# Otomasyon_kart.net
KiCad netlist of a schematic drawn in EAGLE
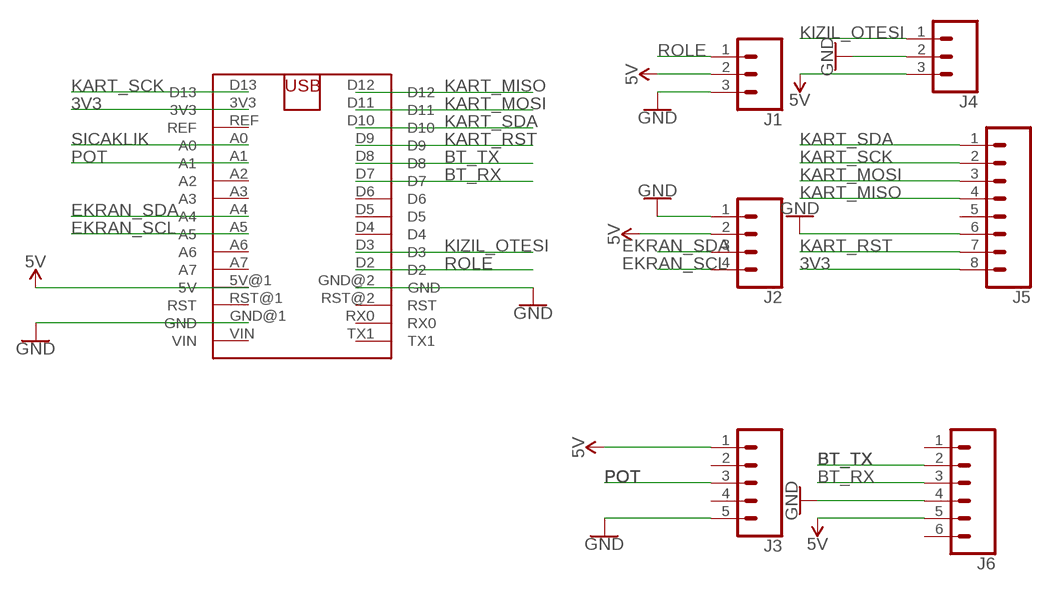
[diagram p0: schematic, sheet 1]

(export (version "E")
  (design (tool "Eeschema 10.0.6"))
  (components
    (comp (ref "J1")
      (value "CONN_03")
      (footprint "eagle-import:1X03")
      (libsource (lib "eagle-import") (part "CONN_03"))
    )
    (comp (ref "J2")
      (value "CONN_04")
      (footprint "eagle-import:1X04")
      (libsource (lib "eagle-import") (part "CONN_04"))
    )
    (comp (ref "J3")
      (value "CONN_05")
      (footprint "eagle-import:1X05")
      (libsource (lib "eagle-import") (part "CONN_05"))
    )
    (comp (ref "J4")
      (value "CONN_03")
      (footprint "eagle-import:1X03")
      (libsource (lib "eagle-import") (part "CONN_03"))
    )
    (comp (ref "J5")
      (value "CONN_08\"")
      (footprint "eagle-import:1X08")
      (libsource (lib "eagle-import") (part "CONN_08{dblquote}"))
    )
    (comp (ref "J6")
      (value "CONN_06LOCK")
      (footprint "eagle-import:1X06_LOCK")
      (libsource (lib "eagle-import") (part "CONN_06LOCK"))
    )
    (comp (ref "U$1")
      (value "ARDUINO_NANO")
      (footprint "eagle-import:ARDUINO_NANO")
      (libsource (lib "eagle-import") (part "ARDUINO_NANO"))
    )
  )
  (nets
    (net (code "1") (name "/3V3") (class "Default")
      (node (ref "J5") (pin "8") (pinfunction "8_8") (pintype "passive"))
      (node (ref "U$1") (pin "3V3") (pinfunction "3V3_3V3") (pintype "bidirectional"))
    )
    (net (code "2") (name "/BT_RX") (class "Default")
      (node (ref "J6") (pin "3") (pinfunction "3_3") (pintype "passive"))
      (node (ref "U$1") (pin "D7") (pinfunction "D7_D7") (pintype "bidirectional"))
    )
    (net (code "3") (name "/BT_TX") (class "Default")
      (node (ref "J6") (pin "2") (pinfunction "2_2") (pintype "passive"))
      (node (ref "U$1") (pin "D8") (pinfunction "D8_D8") (pintype "bidirectional"))
    )
    (net (code "4") (name "/EKRAN_SCL") (class "Default")
      (node (ref "J2") (pin "4") (pinfunction "4_4") (pintype "passive"))
      (node (ref "U$1") (pin "A5") (pinfunction "A5_A5") (pintype "bidirectional"))
    )
    (net (code "5") (name "/EKRAN_SDA") (class "Default")
      (node (ref "J2") (pin "3") (pinfunction "3_3") (pintype "passive"))
      (node (ref "U$1") (pin "A4") (pinfunction "A4_A4") (pintype "bidirectional"))
    )
    (net (code "6") (name "/KART_MISO") (class "Default")
      (node (ref "J5") (pin "4") (pinfunction "4_4") (pintype "passive"))
      (node (ref "U$1") (pin "D12") (pinfunction "D12_D12") (pintype "bidirectional"))
    )
    (net (code "7") (name "/KART_MOSI") (class "Default")
      (node (ref "J5") (pin "3") (pinfunction "3_3") (pintype "passive"))
      (node (ref "U$1") (pin "D11") (pinfunction "D11_D11") (pintype "bidirectional"))
    )
    (net (code "8") (name "/KART_RST") (class "Default")
      (node (ref "J5") (pin "7") (pinfunction "7_7") (pintype "passive"))
      (node (ref "U$1") (pin "D9") (pinfunction "D9_D9") (pintype "bidirectional"))
    )
    (net (code "9") (name "/KART_SCK") (class "Default")
      (node (ref "J5") (pin "2") (pinfunction "2_2") (pintype "passive"))
      (node (ref "U$1") (pin "D13") (pinfunction "D13_D13") (pintype "bidirectional"))
    )
    (net (code "10") (name "/KART_SDA") (class "Default")
      (node (ref "J5") (pin "1") (pinfunction "1_1") (pintype "passive"))
      (node (ref "U$1") (pin "D10") (pinfunction "D10_D10") (pintype "bidirectional"))
    )
    (net (code "11") (name "/KIZIL_OTESI") (class "Default")
      (node (ref "J4") (pin "1") (pinfunction "1_1") (pintype "passive"))
      (node (ref "U$1") (pin "D3") (pinfunction "D3_D3") (pintype "bidirectional"))
    )
    (net (code "12") (name "/POT") (class "Default")
      (node (ref "J3") (pin "3") (pinfunction "3_3") (pintype "passive"))
      (node (ref "U$1") (pin "A1") (pinfunction "A1_A1") (pintype "bidirectional"))
    )
    (net (code "13") (name "/ROLE") (class "Default")
      (node (ref "J1") (pin "1") (pinfunction "1_1") (pintype "passive"))
      (node (ref "U$1") (pin "D2") (pinfunction "D2_D2") (pintype "bidirectional"))
    )
    (net (code "14") (name "/SICAKLIK") (class "Default")
      (node (ref "U$1") (pin "A0") (pinfunction "A0_A0") (pintype "bidirectional"))
    )
    (net (code "15") (name "5V") (class "Default")
      (node (ref "J1") (pin "2") (pinfunction "2_2") (pintype "passive"))
      (node (ref "J2") (pin "2") (pinfunction "2_2") (pintype "passive"))
      (node (ref "J3") (pin "1") (pinfunction "1_1") (pintype "passive"))
      (node (ref "J4") (pin "3") (pinfunction "3_3") (pintype "passive"))
      (node (ref "J6") (pin "5") (pinfunction "5_5") (pintype "passive"))
      (node (ref "U$1") (pin "5V@1") (pinfunction "5V_5V@1") (pintype "bidirectional"))
    )
    (net (code "16") (name "GND") (class "Default")
      (node (ref "J1") (pin "3") (pinfunction "3_3") (pintype "passive"))
      (node (ref "J2") (pin "1") (pinfunction "1_1") (pintype "passive"))
      (node (ref "J3") (pin "5") (pinfunction "5_5") (pintype "passive"))
      (node (ref "J4") (pin "2") (pinfunction "2_2") (pintype "passive"))
      (node (ref "J5") (pin "6") (pinfunction "6_6") (pintype "passive"))
      (node (ref "J6") (pin "4") (pinfunction "4_4") (pintype "passive"))
      (node (ref "U$1") (pin "GND@1") (pinfunction "GND_GND@1") (pintype "bidirectional"))
      (node (ref "U$1") (pin "GND@2") (pinfunction "GND_GND@2") (pintype "bidirectional"))
    )
    (net (code "17") (name "unconnected-(J3-Pad2)") (class "Default")
      (node (ref "J3") (pin "2") (pinfunction "2_2") (pintype "passive"))
    )
    (net (code "18") (name "unconnected-(J3-Pad4)") (class "Default")
      (node (ref "J3") (pin "4") (pinfunction "4_4") (pintype "passive"))
    )
    (net (code "19") (name "unconnected-(J5-Pad5)") (class "Default")
      (node (ref "J5") (pin "5") (pinfunction "5_5") (pintype "passive"))
    )
    (net (code "20") (name "unconnected-(J6-Pad1)") (class "Default")
      (node (ref "J6") (pin "1") (pinfunction "1_1") (pintype "passive"))
    )
    (net (code "21") (name "unconnected-(J6-Pad6)") (class "Default")
      (node (ref "J6") (pin "6") (pinfunction "6_6") (pintype "passive"))
    )
    (net (code "22") (name "unconnected-(U$1-PadA2)") (class "Default")
      (node (ref "U$1") (pin "A2") (pinfunction "A2_A2") (pintype "bidirectional"))
    )
    (net (code "23") (name "unconnected-(U$1-PadA3)") (class "Default")
      (node (ref "U$1") (pin "A3") (pinfunction "A3_A3") (pintype "bidirectional"))
    )
    (net (code "24") (name "unconnected-(U$1-PadA6)") (class "Default")
      (node (ref "U$1") (pin "A6") (pinfunction "A6_A6") (pintype "bidirectional"))
    )
    (net (code "25") (name "unconnected-(U$1-PadA7)") (class "Default")
      (node (ref "U$1") (pin "A7") (pinfunction "A7_A7") (pintype "bidirectional"))
    )
    (net (code "26") (name "unconnected-(U$1-PadD4)") (class "Default")
      (node (ref "U$1") (pin "D4") (pinfunction "D4_D4") (pintype "bidirectional"))
    )
    (net (code "27") (name "unconnected-(U$1-PadD5)") (class "Default")
      (node (ref "U$1") (pin "D5") (pinfunction "D5_D5") (pintype "bidirectional"))
    )
    (net (code "28") (name "unconnected-(U$1-PadD6)") (class "Default")
      (node (ref "U$1") (pin "D6") (pinfunction "D6_D6") (pintype "bidirectional"))
    )
    (net (code "29") (name "unconnected-(U$1-PadREF)") (class "Default")
      (node (ref "U$1") (pin "REF") (pinfunction "REF_REF") (pintype "bidirectional"))
    )
    (net (code "30") (name "unconnected-(U$1-PadRX0)") (class "Default")
      (node (ref "U$1") (pin "RX0") (pinfunction "RX0_RX0") (pintype "bidirectional"))
    )
    (net (code "31") (name "unconnected-(U$1-PadTX1)") (class "Default")
      (node (ref "U$1") (pin "TX1") (pinfunction "TX1_TX1") (pintype "bidirectional"))
    )
    (net (code "32") (name "unconnected-(U$1-PadVIN)") (class "Default")
      (node (ref "U$1") (pin "VIN") (pinfunction "VIN_VIN") (pintype "bidirectional"))
    )
    (net (code "33") (name "unconnected-(U$1-RST-PadRST@1)") (class "Default")
      (node (ref "U$1") (pin "RST@1") (pinfunction "RST_RST@1") (pintype "bidirectional"))
    )
    (net (code "34") (name "unconnected-(U$1-RST-PadRST@2)") (class "Default")
      (node (ref "U$1") (pin "RST@2") (pinfunction "RST_RST@2") (pintype "bidirectional"))
    )
  )
)
